# MCU.net
KiCad netlist of a schematic drawn in Altium Designer
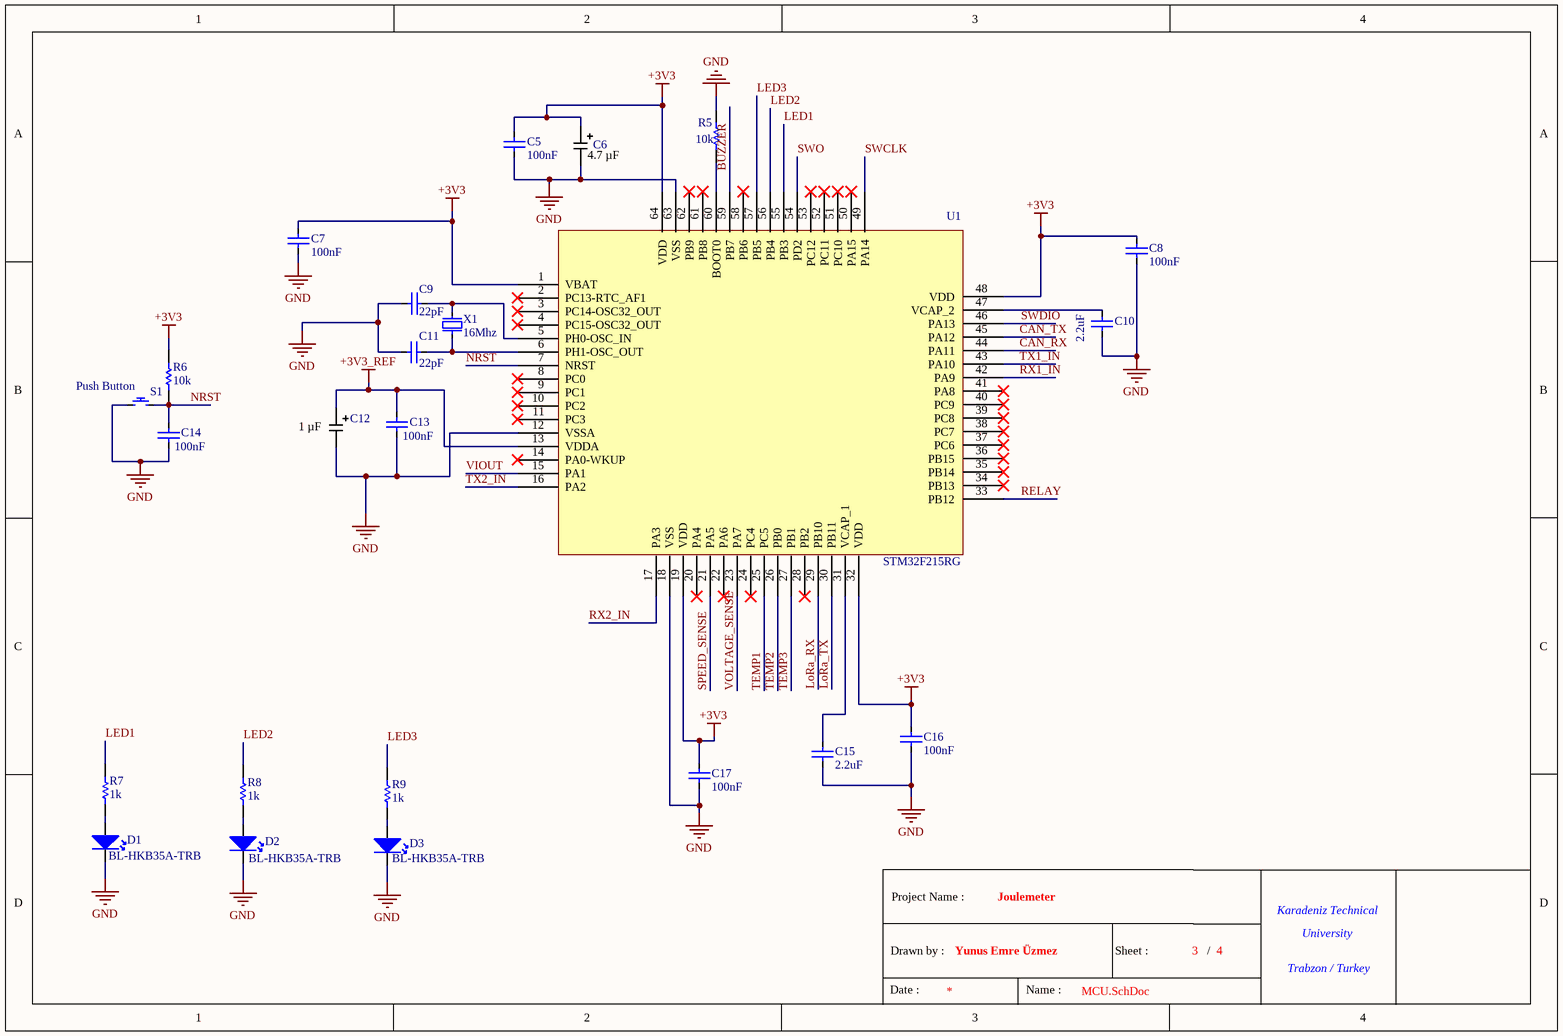
[diagram p0: MCU.SchDoc]

(export (version "E")
  (design (tool "Eeschema 10.0.6"))
  (components
    (comp (ref "C5")
      (value "100nF")
      (footprint "CAP-0603")
      (fields
        (field (name "MANUFACTURER") "TDK")
        (field (name "VOLTAGE") "50V")
        (field (name "TOLERANCE") "%10")
      )
      (libsource (lib "Motor_Driver") (part "CGA3E2X7R1H104K080AA"))
    )
    (comp (ref "C6")
      (value "T491B475K016AT")
      (footprint "KEMET_CAP_TAN-B")
      (description "CAP TANT 4.7UF 10% 16V 1411")
      (fields
        (field (name "MANUFACTURER") "KEMET")
        (field (name "TOLERANCE") "±10%")
        (field (name "CAPACITANCE") "4.7 µF")
      )
      (libsource (lib "Tantalum Capacitors") (part "T491B475K016AT"))
    )
    (comp (ref "C7")
      (value "100nF")
      (footprint "CAP-0603")
      (fields
        (field (name "MANUFACTURER") "TDK")
        (field (name "VOLTAGE") "50V")
        (field (name "TOLERANCE") "%10")
      )
      (libsource (lib "Motor_Driver") (part "CGA3E2X7R1H104K080AA"))
    )
    (comp (ref "C8")
      (value "100nF")
      (footprint "CAP-0603")
      (fields
        (field (name "MANUFACTURER") "TDK")
        (field (name "VOLTAGE") "50V")
        (field (name "TOLERANCE") "%10")
      )
      (libsource (lib "Motor_Driver") (part "CGA3E2X7R1H104K080AA"))
    )
    (comp (ref "C9")
      (value "22pF")
      (footprint "Motor_Driver:CAP-0805")
      (fields
        (field (name "MANUFACTURER") "Samsung Electro-Mechanics")
        (field (name "VOLTAGE") "50V")
        (field (name "TOLERANCE") "%5")
      )
      (libsource (lib "My_Libs") (part "CL21C220JBANNNC"))
    )
    (comp (ref "C10")
      (value "2.2uF")
      (footprint "CAP-0805")
      (fields
        (field (name "MANUFACTURER") "Samsung Electro-Mechanics")
        (field (name "TOLERANCE") "%10")
        (field (name "VOLTAGE") "25V")
      )
      (libsource (lib "Motor_Driver") (part "CL21B225KAFVPNE_1"))
    )
    (comp (ref "C11")
      (value "22pF")
      (footprint "Motor_Driver:CAP-0805")
      (fields
        (field (name "MANUFACTURER") "Samsung Electro-Mechanics")
        (field (name "VOLTAGE") "50V")
        (field (name "TOLERANCE") "%5")
      )
      (libsource (lib "My_Libs") (part "CL21C220JBANNNC"))
    )
    (comp (ref "C12")
      (value "T491B105K025AT")
      (footprint "KEMET_CAP_TAN-B")
      (description "CAP TANT 1UF 10% 25V 1411")
      (fields
        (field (name "MANUFACTURER") "KEMET")
        (field (name "TOLERANCE") "±10%")
        (field (name "CAPACITANCE") "1 µF")
      )
      (libsource (lib "Tantalum Capacitors") (part "T491B105K025AT"))
    )
    (comp (ref "C13")
      (value "100nF")
      (footprint "CAP-0603")
      (fields
        (field (name "MANUFACTURER") "TDK")
        (field (name "VOLTAGE") "50V")
        (field (name "TOLERANCE") "%10")
      )
      (libsource (lib "Motor_Driver") (part "CGA3E2X7R1H104K080AA"))
    )
    (comp (ref "C14")
      (value "100nF")
      (footprint "CAP-0603")
      (fields
        (field (name "MANUFACTURER") "TDK")
        (field (name "VOLTAGE") "50V")
        (field (name "TOLERANCE") "%10")
      )
      (libsource (lib "Motor_Driver") (part "CGA3E2X7R1H104K080AA"))
    )
    (comp (ref "C15")
      (value "2.2uF")
      (footprint "CAP-0805")
      (fields
        (field (name "MANUFACTURER") "Samsung Electro-Mechanics")
        (field (name "TOLERANCE") "%10")
        (field (name "VOLTAGE") "25V")
      )
      (libsource (lib "Motor_Driver") (part "CL21B225KAFVPNE_1"))
    )
    (comp (ref "C16")
      (value "100nF")
      (footprint "CAP-0603")
      (fields
        (field (name "MANUFACTURER") "TDK")
        (field (name "VOLTAGE") "50V")
        (field (name "TOLERANCE") "%10")
      )
      (libsource (lib "Motor_Driver") (part "CGA3E2X7R1H104K080AA"))
    )
    (comp (ref "C17")
      (value "100nF")
      (footprint "CAP-0603")
      (fields
        (field (name "MANUFACTURER") "TDK")
        (field (name "VOLTAGE") "50V")
        (field (name "TOLERANCE") "%10")
      )
      (libsource (lib "Motor_Driver") (part "CGA3E2X7R1H104K080AA"))
    )
    (comp (ref "D1")
      (value "BL-HKB35A-TRB")
      (footprint "LED-0805")
      (fields (field (name "MANUFACTURER") "BRIGHT LED"))
      (libsource (lib "Motor_Driver") (part "BL-HKB35A-TRB"))
    )
    (comp (ref "D2")
      (value "BL-HKB35A-TRB")
      (footprint "LED-0805")
      (fields (field (name "MANUFACTURER") "BRIGHT LED"))
      (libsource (lib "Motor_Driver") (part "BL-HKB35A-TRB"))
    )
    (comp (ref "D3")
      (value "BL-HKB35A-TRB")
      (footprint "LED-0805")
      (fields (field (name "MANUFACTURER") "BRIGHT LED"))
      (libsource (lib "Motor_Driver") (part "BL-HKB35A-TRB"))
    )
    (comp (ref "R5")
      (value "10k")
      (footprint "Motor_Driver:RES-0603")
      (fields
        (field (name "MANUFACTURER") "Vishay")
        (field (name "TOLERANCE") "%1")
        (field (name "POWER") "0.1W")
      )
      (libsource (lib "My_Libs") (part "CRCW060310K0FKEA"))
    )
    (comp (ref "R6")
      (value "10k")
      (footprint "Motor_Driver:RES-0603")
      (fields
        (field (name "MANUFACTURER") "Vishay")
        (field (name "TOLERANCE") "%1")
        (field (name "POWER") "0.1W")
      )
      (libsource (lib "My_Libs") (part "CRCW060310K0FKEA"))
    )
    (comp (ref "R7")
      (value "1k")
      (footprint "Motor_Driver:RES-0603")
      (fields
        (field (name "MANUFACTURER") "Vishay")
        (field (name "TOLERANCE") "%1")
        (field (name "POWER") "0.1W")
      )
      (libsource (lib "My_Libs") (part "CRCW06031K00FKEAC"))
    )
    (comp (ref "R8")
      (value "1k")
      (footprint "Motor_Driver:RES-0603")
      (fields
        (field (name "MANUFACTURER") "Vishay")
        (field (name "TOLERANCE") "%1")
        (field (name "POWER") "0.1W")
      )
      (libsource (lib "My_Libs") (part "CRCW06031K00FKEAC"))
    )
    (comp (ref "R9")
      (value "1k")
      (footprint "Motor_Driver:RES-0603")
      (fields
        (field (name "MANUFACTURER") "Vishay")
        (field (name "TOLERANCE") "%1")
        (field (name "POWER") "0.1W")
      )
      (libsource (lib "My_Libs") (part "CRCW06031K00FKEAC"))
    )
    (comp (ref "S1")
      (value "Push Button")
      (footprint "2.54mm_Push Button")
      (libsource (lib "Motor_Driver") (part "Push Button"))
    )
    (comp (ref "U1")
      (value "STM32F215RG")
      (footprint "LQFP64")
      (fields (field (name "MANUFACTURER") "STM"))
      (libsource (lib "jl_lib") (part "STM32F215RG"))
    )
    (comp (ref "X1")
      (value "16Mhz")
      (footprint "Motor_Driver:OSC-THT (11.5*5.00*3.60)")
      (fields (field (name "MANUFACTURER") "ANSEN"))
      (libsource (lib "My_Libs") (part "AS49S-16M-FC160F3"))
    )
  )
  (nets
    (net (code "1") (name "+3V3") (class "Default")
      (node (ref "C16") (pin "2") (pinfunction "2_2") (pintype "passive"))
      (node (ref "C17") (pin "2") (pinfunction "2_2") (pintype "passive"))
      (node (ref "C5") (pin "2") (pinfunction "2_2") (pintype "passive"))
      (node (ref "C6") (pin "1") (pinfunction "1_1") (pintype "passive"))
      (node (ref "C7") (pin "2") (pinfunction "2_2") (pintype "passive"))
      (node (ref "C8") (pin "2") (pinfunction "2_2") (pintype "passive"))
      (node (ref "R6") (pin "1") (pinfunction "1_1") (pintype "passive"))
      (node (ref "U1") (pin "1") (pinfunction "VBAT_1") (pintype "passive"))
      (node (ref "U1") (pin "19") (pinfunction "VDD_19") (pintype "passive"))
      (node (ref "U1") (pin "32") (pinfunction "VDD_32") (pintype "passive"))
      (node (ref "U1") (pin "48") (pinfunction "VDD_48") (pintype "passive"))
      (node (ref "U1") (pin "64") (pinfunction "VDD_64") (pintype "passive"))
    )
    (net (code "2") (name "+3V3_REF") (class "Default")
      (node (ref "C12") (pin "1") (pinfunction "1_1") (pintype "passive"))
      (node (ref "C13") (pin "2") (pinfunction "2_2") (pintype "passive"))
      (node (ref "U1") (pin "13") (pinfunction "VDDA_13") (pintype "passive"))
    )
    (net (code "3") (name "/BUZZER") (class "Default")
      (node (ref "U1") (pin "59") (pinfunction "PB7_59") (pintype "passive"))
    )
    (net (code "4") (name "/CAN_RX") (class "Default")
      (node (ref "U1") (pin "44") (pinfunction "PA11_44") (pintype "passive"))
    )
    (net (code "5") (name "/CAN_TX") (class "Default")
      (node (ref "U1") (pin "45") (pinfunction "PA12_45") (pintype "passive"))
    )
    (net (code "6") (name "/LED1") (class "Default")
      (node (ref "R7") (pin "1") (pinfunction "1_1") (pintype "passive"))
      (node (ref "U1") (pin "55") (pinfunction "PB3_55") (pintype "passive"))
    )
    (net (code "7") (name "/LED2") (class "Default")
      (node (ref "R8") (pin "1") (pinfunction "1_1") (pintype "passive"))
      (node (ref "U1") (pin "56") (pinfunction "PB4_56") (pintype "passive"))
    )
    (net (code "8") (name "/LED3") (class "Default")
      (node (ref "R9") (pin "1") (pinfunction "1_1") (pintype "passive"))
      (node (ref "U1") (pin "57") (pinfunction "PB5_57") (pintype "passive"))
    )
    (net (code "9") (name "/LoRa_RX") (class "Default")
      (node (ref "U1") (pin "29") (pinfunction "PB10_29") (pintype "passive"))
    )
    (net (code "10") (name "/LoRa_TX") (class "Default")
      (node (ref "U1") (pin "30") (pinfunction "PB11_30") (pintype "passive"))
    )
    (net (code "11") (name "/NRST") (class "Default")
      (node (ref "C14") (pin "2") (pinfunction "2_2") (pintype "passive"))
      (node (ref "R6") (pin "2") (pinfunction "2_2") (pintype "passive"))
      (node (ref "S1") (pin "2") (pinfunction "2_2") (pintype "passive"))
      (node (ref "U1") (pin "7") (pinfunction "NRST_7") (pintype "passive"))
    )
    (net (code "12") (name "/RELAY") (class "Default")
      (node (ref "U1") (pin "33") (pinfunction "PB12_33") (pintype "passive"))
    )
    (net (code "13") (name "/RX1_IN") (class "Default")
      (node (ref "U1") (pin "42") (pinfunction "PA9_42") (pintype "passive"))
    )
    (net (code "14") (name "/RX2_IN") (class "Default")
      (node (ref "U1") (pin "17") (pinfunction "PA3_17") (pintype "passive"))
    )
    (net (code "15") (name "/SPEED_SENSE") (class "Default")
      (node (ref "U1") (pin "21") (pinfunction "PA5_21") (pintype "passive"))
    )
    (net (code "16") (name "/SWCLK") (class "Default")
      (node (ref "U1") (pin "49") (pinfunction "PA14_49") (pintype "passive"))
    )
    (net (code "17") (name "/SWDIO") (class "Default")
      (node (ref "U1") (pin "46") (pinfunction "PA13_46") (pintype "passive"))
    )
    (net (code "18") (name "/SWO") (class "Default")
      (node (ref "U1") (pin "54") (pinfunction "PD2_54") (pintype "passive"))
    )
    (net (code "19") (name "/TEMP1") (class "Default")
      (node (ref "U1") (pin "25") (pinfunction "PC5_25") (pintype "passive"))
    )
    (net (code "20") (name "/TEMP2") (class "Default")
      (node (ref "U1") (pin "26") (pinfunction "PB0_26") (pintype "passive"))
    )
    (net (code "21") (name "/TEMP3") (class "Default")
      (node (ref "U1") (pin "27") (pinfunction "PB1_27") (pintype "passive"))
    )
    (net (code "22") (name "/TX1_IN") (class "Default")
      (node (ref "U1") (pin "43") (pinfunction "PA10_43") (pintype "passive"))
    )
    (net (code "23") (name "/TX2_IN") (class "Default")
      (node (ref "U1") (pin "16") (pinfunction "PA2_16") (pintype "passive"))
    )
    (net (code "24") (name "/VIOUT") (class "Default")
      (node (ref "U1") (pin "15") (pinfunction "PA1_15") (pintype "passive"))
    )
    (net (code "25") (name "/VOLTAGE_SENSE") (class "Default")
      (node (ref "U1") (pin "23") (pinfunction "PA7_23") (pintype "passive"))
    )
    (net (code "26") (name "GND") (class "Default")
      (node (ref "C10") (pin "1") (pinfunction "1_1") (pintype "passive"))
      (node (ref "C11") (pin "1") (pinfunction "1_1") (pintype "passive"))
      (node (ref "C12") (pin "2") (pinfunction "2_2") (pintype "passive"))
      (node (ref "C13") (pin "1") (pinfunction "1_1") (pintype "passive"))
      (node (ref "C14") (pin "1") (pinfunction "1_1") (pintype "passive"))
      (node (ref "C15") (pin "1") (pinfunction "1_1") (pintype "passive"))
      (node (ref "C16") (pin "1") (pinfunction "1_1") (pintype "passive"))
      (node (ref "C17") (pin "1") (pinfunction "1_1") (pintype "passive"))
      (node (ref "C5") (pin "1") (pinfunction "1_1") (pintype "passive"))
      (node (ref "C6") (pin "2") (pinfunction "2_2") (pintype "passive"))
      (node (ref "C7") (pin "1") (pinfunction "1_1") (pintype "passive"))
      (node (ref "C8") (pin "1") (pinfunction "1_1") (pintype "passive"))
      (node (ref "C9") (pin "2") (pinfunction "2_2") (pintype "passive"))
      (node (ref "D1") (pin "2") (pinfunction "K_2") (pintype "passive"))
      (node (ref "D2") (pin "2") (pinfunction "K_2") (pintype "passive"))
      (node (ref "D3") (pin "2") (pinfunction "K_2") (pintype "passive"))
      (node (ref "R5") (pin "2") (pinfunction "2_2") (pintype "passive"))
      (node (ref "S1") (pin "1") (pinfunction "1_1") (pintype "passive"))
      (node (ref "U1") (pin "12") (pinfunction "VSSA_12") (pintype "passive"))
      (node (ref "U1") (pin "18") (pinfunction "VSS_18") (pintype "passive"))
      (node (ref "U1") (pin "63") (pinfunction "VSS_63") (pintype "passive"))
    )
    (net (code "27") (name "Net-(D1-A)") (class "Default")
      (node (ref "D1") (pin "1") (pinfunction "A_1") (pintype "passive"))
      (node (ref "R7") (pin "2") (pinfunction "2_2") (pintype "passive"))
    )
    (net (code "28") (name "Net-(D2-A)") (class "Default")
      (node (ref "D2") (pin "1") (pinfunction "A_1") (pintype "passive"))
      (node (ref "R8") (pin "2") (pinfunction "2_2") (pintype "passive"))
    )
    (net (code "29") (name "Net-(D3-A)") (class "Default")
      (node (ref "D3") (pin "1") (pinfunction "A_1") (pintype "passive"))
      (node (ref "R9") (pin "2") (pinfunction "2_2") (pintype "passive"))
    )
    (net (code "30") (name "Net-(U1-BOOT0)") (class "Default")
      (node (ref "R5") (pin "1") (pinfunction "1_1") (pintype "passive"))
      (node (ref "U1") (pin "60") (pinfunction "BOOT0_60") (pintype "passive"))
    )
    (net (code "31") (name "Net-(U1-PH0-OSC_IN)") (class "Default")
      (node (ref "C9") (pin "1") (pinfunction "1_1") (pintype "passive"))
      (node (ref "U1") (pin "5") (pinfunction "PH0-OSC_IN_5") (pintype "passive"))
      (node (ref "X1") (pin "2") (pinfunction "2_2") (pintype "passive"))
    )
    (net (code "32") (name "Net-(U1-PH1-OSC_OUT)") (class "Default")
      (node (ref "C11") (pin "2") (pinfunction "2_2") (pintype "passive"))
      (node (ref "U1") (pin "6") (pinfunction "PH1-OSC_OUT_6") (pintype "passive"))
      (node (ref "X1") (pin "1") (pinfunction "1_1") (pintype "passive"))
    )
    (net (code "33") (name "Net-(U1-VCAP_1)") (class "Default")
      (node (ref "C15") (pin "2") (pinfunction "2_2") (pintype "passive"))
      (node (ref "U1") (pin "31") (pinfunction "VCAP_1_31") (pintype "passive"))
    )
    (net (code "34") (name "Net-(U1-VCAP_2)") (class "Default")
      (node (ref "C10") (pin "2") (pinfunction "2_2") (pintype "passive"))
      (node (ref "U1") (pin "47") (pinfunction "VCAP_2_47") (pintype "passive"))
    )
    (net (code "35") (name "unconnected-(U1-PA0-WKUP-Pad14)") (class "Default")
      (node (ref "U1") (pin "14") (pinfunction "PA0-WKUP_14") (pintype "passive+no_connect"))
    )
    (net (code "36") (name "unconnected-(U1-PA4-Pad20)") (class "Default")
      (node (ref "U1") (pin "20") (pinfunction "PA4_20") (pintype "passive+no_connect"))
    )
    (net (code "37") (name "unconnected-(U1-PA6-Pad22)") (class "Default")
      (node (ref "U1") (pin "22") (pinfunction "PA6_22") (pintype "passive+no_connect"))
    )
    (net (code "38") (name "unconnected-(U1-PA8-Pad41)") (class "Default")
      (node (ref "U1") (pin "41") (pinfunction "PA8_41") (pintype "passive+no_connect"))
    )
    (net (code "39") (name "unconnected-(U1-PA15-Pad50)") (class "Default")
      (node (ref "U1") (pin "50") (pinfunction "PA15_50") (pintype "passive+no_connect"))
    )
    (net (code "40") (name "unconnected-(U1-PB2-Pad28)") (class "Default")
      (node (ref "U1") (pin "28") (pinfunction "PB2_28") (pintype "passive+no_connect"))
    )
    (net (code "41") (name "unconnected-(U1-PB6-Pad58)") (class "Default")
      (node (ref "U1") (pin "58") (pinfunction "PB6_58") (pintype "passive+no_connect"))
    )
    (net (code "42") (name "unconnected-(U1-PB8-Pad61)") (class "Default")
      (node (ref "U1") (pin "61") (pinfunction "PB8_61") (pintype "passive+no_connect"))
    )
    (net (code "43") (name "unconnected-(U1-PB9-Pad62)") (class "Default")
      (node (ref "U1") (pin "62") (pinfunction "PB9_62") (pintype "passive+no_connect"))
    )
    (net (code "44") (name "unconnected-(U1-PB13-Pad34)") (class "Default")
      (node (ref "U1") (pin "34") (pinfunction "PB13_34") (pintype "passive+no_connect"))
    )
    (net (code "45") (name "unconnected-(U1-PB14-Pad35)") (class "Default")
      (node (ref "U1") (pin "35") (pinfunction "PB14_35") (pintype "passive+no_connect"))
    )
    (net (code "46") (name "unconnected-(U1-PB15-Pad36)") (class "Default")
      (node (ref "U1") (pin "36") (pinfunction "PB15_36") (pintype "passive+no_connect"))
    )
    (net (code "47") (name "unconnected-(U1-PC0-Pad8)") (class "Default")
      (node (ref "U1") (pin "8") (pinfunction "PC0_8") (pintype "passive+no_connect"))
    )
    (net (code "48") (name "unconnected-(U1-PC1-Pad9)") (class "Default")
      (node (ref "U1") (pin "9") (pinfunction "PC1_9") (pintype "passive+no_connect"))
    )
    (net (code "49") (name "unconnected-(U1-PC2-Pad10)") (class "Default")
      (node (ref "U1") (pin "10") (pinfunction "PC2_10") (pintype "passive+no_connect"))
    )
    (net (code "50") (name "unconnected-(U1-PC3-Pad11)") (class "Default")
      (node (ref "U1") (pin "11") (pinfunction "PC3_11") (pintype "passive+no_connect"))
    )
    (net (code "51") (name "unconnected-(U1-PC4-Pad24)") (class "Default")
      (node (ref "U1") (pin "24") (pinfunction "PC4_24") (pintype "passive+no_connect"))
    )
    (net (code "52") (name "unconnected-(U1-PC6-Pad37)") (class "Default")
      (node (ref "U1") (pin "37") (pinfunction "PC6_37") (pintype "passive+no_connect"))
    )
    (net (code "53") (name "unconnected-(U1-PC7-Pad38)") (class "Default")
      (node (ref "U1") (pin "38") (pinfunction "PC7_38") (pintype "passive+no_connect"))
    )
    (net (code "54") (name "unconnected-(U1-PC8-Pad39)") (class "Default")
      (node (ref "U1") (pin "39") (pinfunction "PC8_39") (pintype "passive+no_connect"))
    )
    (net (code "55") (name "unconnected-(U1-PC9-Pad40)") (class "Default")
      (node (ref "U1") (pin "40") (pinfunction "PC9_40") (pintype "passive+no_connect"))
    )
    (net (code "56") (name "unconnected-(U1-PC10-Pad51)") (class "Default")
      (node (ref "U1") (pin "51") (pinfunction "PC10_51") (pintype "passive+no_connect"))
    )
    (net (code "57") (name "unconnected-(U1-PC11-Pad52)") (class "Default")
      (node (ref "U1") (pin "52") (pinfunction "PC11_52") (pintype "passive+no_connect"))
    )
    (net (code "58") (name "unconnected-(U1-PC12-Pad53)") (class "Default")
      (node (ref "U1") (pin "53") (pinfunction "PC12_53") (pintype "passive+no_connect"))
    )
    (net (code "59") (name "unconnected-(U1-PC13-RTC_AF1-Pad2)") (class "Default")
      (node (ref "U1") (pin "2") (pinfunction "PC13-RTC_AF1_2") (pintype "passive+no_connect"))
    )
    (net (code "60") (name "unconnected-(U1-PC14-OSC32_OUT-Pad3)") (class "Default")
      (node (ref "U1") (pin "3") (pinfunction "PC14-OSC32_OUT_3") (pintype "passive+no_connect"))
    )
    (net (code "61") (name "unconnected-(U1-PC15-OSC32_OUT-Pad4)") (class "Default")
      (node (ref "U1") (pin "4") (pinfunction "PC15-OSC32_OUT_4") (pintype "passive+no_connect"))
    )
  )
)
